# BSPD_rev11_v3.net
KiCad netlist of a schematic drawn in EAGLE
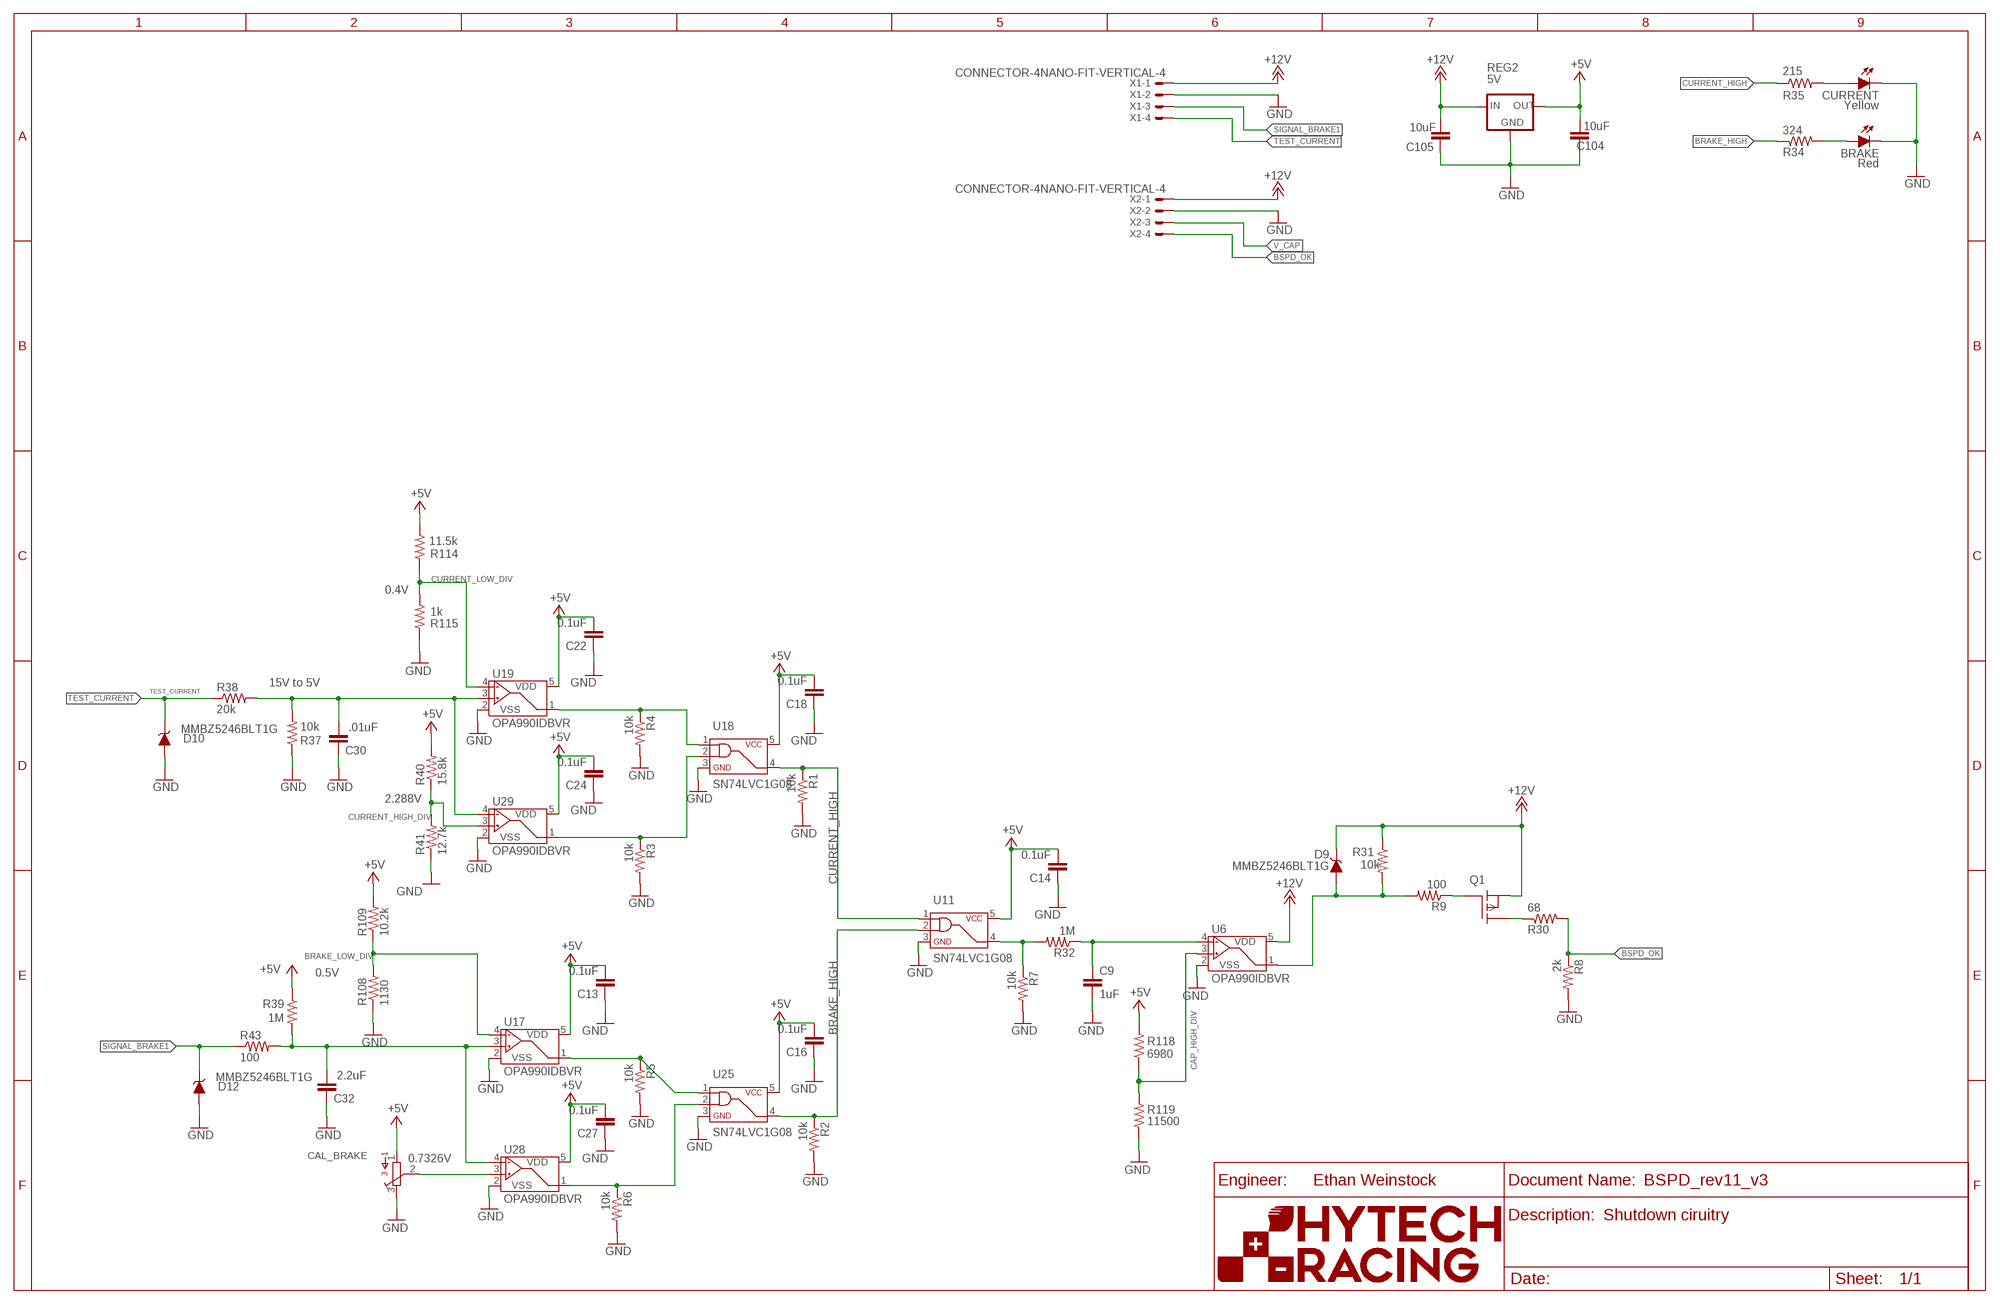
[diagram p0: schematic, sheet 1]

(export (version "E")
  (design (tool "Eeschema 10.0.6"))
  (components
    (comp (ref "BRAKE")
      (value "Red")
      (footprint "eagle-import:LED-805")
      (libsource (lib "eagle-import") (part "LED-0805"))
    )
    (comp (ref "C9")
      (value "1uF")
      (footprint "eagle-import:0603-CAP")
      (libsource (lib "eagle-import") (part "CAP0603-CAP"))
    )
    (comp (ref "C13")
      (value "0.1uF")
      (footprint "eagle-import:0603-CAP")
      (libsource (lib "eagle-import") (part "CAP0603-CAP"))
    )
    (comp (ref "C14")
      (value "0.1uF")
      (footprint "eagle-import:0603-CAP")
      (libsource (lib "eagle-import") (part "CAP0603-CAP"))
    )
    (comp (ref "C16")
      (value "0.1uF")
      (footprint "eagle-import:0603-CAP")
      (libsource (lib "eagle-import") (part "CAP0603-CAP"))
    )
    (comp (ref "C18")
      (value "0.1uF")
      (footprint "eagle-import:0603-CAP")
      (libsource (lib "eagle-import") (part "CAP0603-CAP"))
    )
    (comp (ref "C22")
      (value "0.1uF")
      (footprint "eagle-import:0603-CAP")
      (libsource (lib "eagle-import") (part "CAP0603-CAP"))
    )
    (comp (ref "C24")
      (value "0.1uF")
      (footprint "eagle-import:0603-CAP")
      (libsource (lib "eagle-import") (part "CAP0603-CAP"))
    )
    (comp (ref "C27")
      (value "0.1uF")
      (footprint "eagle-import:0603-CAP")
      (libsource (lib "eagle-import") (part "CAP0603-CAP"))
    )
    (comp (ref "C30")
      (value ".01uF")
      (footprint "eagle-import:0603-CAP")
      (libsource (lib "eagle-import") (part "CAP0603-CAP"))
    )
    (comp (ref "C32")
      (value "2.2uF")
      (footprint "eagle-import:0603-CAP")
      (libsource (lib "eagle-import") (part "CAP0603-CAP"))
    )
    (comp (ref "C104")
      (value "10uF")
      (footprint "eagle-import:0603-CAP")
      (libsource (lib "eagle-import") (part "CAP0603-CAP"))
    )
    (comp (ref "C105")
      (value "10uF")
      (footprint "eagle-import:0603-CAP")
      (libsource (lib "eagle-import") (part "CAP0603-CAP"))
    )
    (comp (ref "CAL_BRAKE")
      (value "TRIMPOT_3296C")
      (footprint "eagle-import:TRIMPOT_3296")
      (libsource (lib "eagle-import") (part "TRIMPOT_3296C"))
    )
    (comp (ref "CURRENT")
      (value "Yellow")
      (footprint "eagle-import:LED-805")
      (libsource (lib "eagle-import") (part "LED-0805"))
    )
    (comp (ref "D9")
      (value "MMBZ5246BLT1G")
      (footprint "eagle-import:SOT23")
      (libsource (lib "eagle-import") (part "DIODE_ZENER"))
    )
    (comp (ref "D10")
      (value "MMBZ5246BLT1G")
      (footprint "eagle-import:SOT23")
      (libsource (lib "eagle-import") (part "DIODE_ZENER"))
    )
    (comp (ref "D12")
      (value "MMBZ5246BLT1G")
      (footprint "eagle-import:SOT23")
      (libsource (lib "eagle-import") (part "DIODE_ZENER"))
    )
    (comp (ref "Q1")
      (value "P-CHANNEL_MOSFET_DMP3099L-7")
      (footprint "eagle-import:SOT23")
      (libsource (lib "eagle-import") (part "P-CHANNEL_MOSFET_DMP3099L-7"))
    )
    (comp (ref "R1")
      (value "10k")
      (footprint "eagle-import:0603-RES")
      (libsource (lib "eagle-import") (part "RESISTOR0603"))
    )
    (comp (ref "R2")
      (value "10k")
      (footprint "eagle-import:0603-RES")
      (libsource (lib "eagle-import") (part "RESISTOR0603"))
    )
    (comp (ref "R3")
      (value "10k")
      (footprint "eagle-import:0603-RES")
      (libsource (lib "eagle-import") (part "RESISTOR0603"))
    )
    (comp (ref "R4")
      (value "10k")
      (footprint "eagle-import:0603-RES")
      (libsource (lib "eagle-import") (part "RESISTOR0603"))
    )
    (comp (ref "R5")
      (value "10k")
      (footprint "eagle-import:0603-RES")
      (libsource (lib "eagle-import") (part "RESISTOR0603"))
    )
    (comp (ref "R6")
      (value "10k")
      (footprint "eagle-import:0603-RES")
      (libsource (lib "eagle-import") (part "RESISTOR0603"))
    )
    (comp (ref "R7")
      (value "10k")
      (footprint "eagle-import:0603-RES")
      (libsource (lib "eagle-import") (part "RESISTOR0603"))
    )
    (comp (ref "R8")
      (value "2k")
      (footprint "eagle-import:0603-RES")
      (libsource (lib "eagle-import") (part "RESISTOR0603"))
    )
    (comp (ref "R9")
      (value "100")
      (footprint "eagle-import:0603-RES")
      (libsource (lib "eagle-import") (part "RESISTOR0603"))
    )
    (comp (ref "R30")
      (value "68")
      (footprint "eagle-import:0603-RES")
      (libsource (lib "eagle-import") (part "RESISTOR0603"))
    )
    (comp (ref "R31")
      (value "10k")
      (footprint "eagle-import:0603-RES")
      (libsource (lib "eagle-import") (part "RESISTOR0603"))
    )
    (comp (ref "R32")
      (value "1M")
      (footprint "eagle-import:0603-RES")
      (libsource (lib "eagle-import") (part "RESISTOR0603"))
    )
    (comp (ref "R34")
      (value "324")
      (footprint "eagle-import:0603-RES")
      (libsource (lib "eagle-import") (part "RESISTOR0603"))
    )
    (comp (ref "R35")
      (value "215")
      (footprint "eagle-import:0603-RES")
      (libsource (lib "eagle-import") (part "RESISTOR0603"))
    )
    (comp (ref "R37")
      (value "10k")
      (footprint "eagle-import:0603-RES")
      (libsource (lib "eagle-import") (part "RESISTOR0603"))
    )
    (comp (ref "R38")
      (value "20k")
      (footprint "eagle-import:0603-RES")
      (libsource (lib "eagle-import") (part "RESISTOR0603"))
    )
    (comp (ref "R39")
      (value "1M")
      (footprint "eagle-import:0603-RES")
      (libsource (lib "eagle-import") (part "RESISTOR0603"))
    )
    (comp (ref "R40")
      (value "15.8k")
      (footprint "eagle-import:0603-RES")
      (libsource (lib "eagle-import") (part "RESISTOR0603"))
    )
    (comp (ref "R41")
      (value "12.7k")
      (footprint "eagle-import:0603-RES")
      (libsource (lib "eagle-import") (part "RESISTOR0603"))
    )
    (comp (ref "R43")
      (value "100")
      (footprint "eagle-import:0603-RES")
      (libsource (lib "eagle-import") (part "RESISTOR0603"))
    )
    (comp (ref "R108")
      (value "1130")
      (footprint "eagle-import:0603-RES")
      (libsource (lib "eagle-import") (part "RESISTOR0603"))
    )
    (comp (ref "R109")
      (value "10.2k")
      (footprint "eagle-import:0603-RES")
      (libsource (lib "eagle-import") (part "RESISTOR0603"))
    )
    (comp (ref "R114")
      (value "11.5k")
      (footprint "eagle-import:0603-RES")
      (libsource (lib "eagle-import") (part "RESISTOR0603"))
    )
    (comp (ref "R115")
      (value "1k")
      (footprint "eagle-import:0603-RES")
      (libsource (lib "eagle-import") (part "RESISTOR0603"))
    )
    (comp (ref "R118")
      (value "6980")
      (footprint "eagle-import:0603-RES")
      (libsource (lib "eagle-import") (part "RESISTOR0603"))
    )
    (comp (ref "R119")
      (value "11500")
      (footprint "eagle-import:0603-RES")
      (libsource (lib "eagle-import") (part "RESISTOR0603"))
    )
    (comp (ref "REG2")
      (value "5V")
      (footprint "eagle-import:OKI-78SR")
      (libsource (lib "eagle-import") (part "OKI-78SR-5"))
    )
    (comp (ref "U6")
      (value "OPA990IDBVR")
      (footprint "eagle-import:SOT-23-5")
      (libsource (lib "eagle-import") (part "OPA990IDBVR"))
    )
    (comp (ref "U11")
      (value "SN74LVC1G08")
      (footprint "eagle-import:SOT-23-5")
      (libsource (lib "eagle-import") (part "SN74LVC1G08"))
    )
    (comp (ref "U17")
      (value "OPA990IDBVR")
      (footprint "eagle-import:SOT-23-5")
      (libsource (lib "eagle-import") (part "OPA990IDBVR"))
    )
    (comp (ref "U18")
      (value "SN74LVC1G08")
      (footprint "eagle-import:SOT-23-5")
      (libsource (lib "eagle-import") (part "SN74LVC1G08"))
    )
    (comp (ref "U19")
      (value "OPA990IDBVR")
      (footprint "eagle-import:SOT-23-5")
      (libsource (lib "eagle-import") (part "OPA990IDBVR"))
    )
    (comp (ref "U25")
      (value "SN74LVC1G08")
      (footprint "eagle-import:SOT-23-5")
      (libsource (lib "eagle-import") (part "SN74LVC1G08"))
    )
    (comp (ref "U28")
      (value "OPA990IDBVR")
      (footprint "eagle-import:SOT-23-5")
      (libsource (lib "eagle-import") (part "OPA990IDBVR"))
    )
    (comp (ref "U29")
      (value "OPA990IDBVR")
      (footprint "eagle-import:SOT-23-5")
      (libsource (lib "eagle-import") (part "OPA990IDBVR"))
    )
    (comp (ref "X1")
      (value "CONNECTOR-4NANO-FIT-VERTICAL-4")
      (footprint "eagle-import:NANO-FIT_VERTICAL-4")
      (libsource (lib "eagle-import") (part "CONNECTOR-4NANO-FIT-VERTICAL-4"))
    )
    (comp (ref "X2")
      (value "CONNECTOR-4NANO-FIT-VERTICAL-4")
      (footprint "eagle-import:NANO-FIT_VERTICAL-4")
      (libsource (lib "eagle-import") (part "CONNECTOR-4NANO-FIT-VERTICAL-4"))
    )
  )
  (nets
    (net (code "1") (name "+5V") (class "Default")
      (node (ref "C104") (pin "2") (pinfunction "2_2") (pintype "passive"))
      (node (ref "C13") (pin "2") (pinfunction "2_2") (pintype "passive"))
      (node (ref "C14") (pin "2") (pinfunction "2_2") (pintype "passive"))
      (node (ref "C16") (pin "2") (pinfunction "2_2") (pintype "passive"))
      (node (ref "C18") (pin "2") (pinfunction "2_2") (pintype "passive"))
      (node (ref "C22") (pin "2") (pinfunction "2_2") (pintype "passive"))
      (node (ref "C24") (pin "2") (pinfunction "2_2") (pintype "passive"))
      (node (ref "C27") (pin "2") (pinfunction "2_2") (pintype "passive"))
      (node (ref "CAL_BRAKE") (pin "1") (pinfunction "1_1") (pintype "passive"))
      (node (ref "R109") (pin "2") (pinfunction "2_2") (pintype "passive"))
      (node (ref "R114") (pin "2") (pinfunction "2_2") (pintype "passive"))
      (node (ref "R118") (pin "2") (pinfunction "2_2") (pintype "passive"))
      (node (ref "R39") (pin "1") (pinfunction "1_1") (pintype "passive"))
      (node (ref "R40") (pin "2") (pinfunction "2_2") (pintype "passive"))
      (node (ref "REG2") (pin "3") (pinfunction "OUT_3") (pintype "passive"))
      (node (ref "U11") (pin "5") (pinfunction "5_5") (pintype "passive"))
      (node (ref "U17") (pin "5") (pinfunction "VDD_5") (pintype "passive"))
      (node (ref "U18") (pin "5") (pinfunction "5_5") (pintype "passive"))
      (node (ref "U19") (pin "5") (pinfunction "VDD_5") (pintype "passive"))
      (node (ref "U25") (pin "5") (pinfunction "5_5") (pintype "passive"))
      (node (ref "U28") (pin "5") (pinfunction "VDD_5") (pintype "passive"))
      (node (ref "U29") (pin "5") (pinfunction "VDD_5") (pintype "passive"))
    )
    (net (code "2") (name "+12V") (class "Default")
      (node (ref "C105") (pin "2") (pinfunction "2_2") (pintype "passive"))
      (node (ref "D9") (pin "3") (pinfunction "C_3") (pintype "passive"))
      (node (ref "Q1") (pin "2") (pinfunction "S_2") (pintype "passive"))
      (node (ref "R31") (pin "1") (pinfunction "1_1") (pintype "passive"))
      (node (ref "REG2") (pin "1") (pinfunction "IN_1") (pintype "input"))
      (node (ref "U6") (pin "5") (pinfunction "VDD_5") (pintype "passive"))
      (node (ref "X1") (pin "P$1") (pinfunction "S_P$1") (pintype "passive"))
      (node (ref "X2") (pin "P$1") (pinfunction "S_P$1") (pintype "passive"))
    )
    (net (code "3") (name "/BRAKE_LOW_DIV") (class "Default")
      (node (ref "R108") (pin "2") (pinfunction "2_2") (pintype "passive"))
      (node (ref "R109") (pin "1") (pinfunction "1_1") (pintype "passive"))
      (node (ref "U17") (pin "4") (pinfunction "VIN-_4") (pintype "passive"))
    )
    (net (code "4") (name "/CAP_HIGH_DIV") (class "Default")
      (node (ref "R118") (pin "1") (pinfunction "1_1") (pintype "passive"))
      (node (ref "R119") (pin "2") (pinfunction "2_2") (pintype "passive"))
      (node (ref "U6") (pin "3") (pinfunction "VIN+_3") (pintype "passive"))
    )
    (net (code "5") (name "/CURRENT_HIGH_DIV") (class "Default")
      (node (ref "R40") (pin "1") (pinfunction "1_1") (pintype "passive"))
      (node (ref "R41") (pin "2") (pinfunction "2_2") (pintype "passive"))
      (node (ref "U29") (pin "3") (pinfunction "VIN+_3") (pintype "passive"))
    )
    (net (code "6") (name "/CURRENT_LOW_DIV") (class "Default")
      (node (ref "R114") (pin "1") (pinfunction "1_1") (pintype "passive"))
      (node (ref "R115") (pin "2") (pinfunction "2_2") (pintype "passive"))
      (node (ref "U19") (pin "4") (pinfunction "VIN-_4") (pintype "passive"))
    )
    (net (code "7") (name "BRAKE_HIGH") (class "Default")
      (node (ref "R2") (pin "1") (pinfunction "1_1") (pintype "passive"))
      (node (ref "R34") (pin "1") (pinfunction "1_1") (pintype "passive"))
      (node (ref "U11") (pin "2") (pinfunction "2_2") (pintype "passive"))
      (node (ref "U25") (pin "4") (pinfunction "4_4") (pintype "passive"))
    )
    (net (code "8") (name "BSPD_OK") (class "Default")
      (node (ref "R30") (pin "2") (pinfunction "2_2") (pintype "passive"))
      (node (ref "R8") (pin "1") (pinfunction "1_1") (pintype "passive"))
      (node (ref "X2") (pin "P$4") (pinfunction "S_P$4") (pintype "passive"))
    )
    (net (code "9") (name "CURRENT_HIGH") (class "Default")
      (node (ref "R1") (pin "1") (pinfunction "1_1") (pintype "passive"))
      (node (ref "R35") (pin "1") (pinfunction "1_1") (pintype "passive"))
      (node (ref "U11") (pin "1") (pinfunction "1_1") (pintype "passive"))
      (node (ref "U18") (pin "4") (pinfunction "4_4") (pintype "passive"))
    )
    (net (code "10") (name "GND") (class "Default")
      (node (ref "BRAKE") (pin "C") (pinfunction "C_C") (pintype "passive"))
      (node (ref "C104") (pin "1") (pinfunction "1_1") (pintype "passive"))
      (node (ref "C105") (pin "1") (pinfunction "1_1") (pintype "passive"))
      (node (ref "C13") (pin "1") (pinfunction "1_1") (pintype "passive"))
      (node (ref "C14") (pin "1") (pinfunction "1_1") (pintype "passive"))
      (node (ref "C16") (pin "1") (pinfunction "1_1") (pintype "passive"))
      (node (ref "C18") (pin "1") (pinfunction "1_1") (pintype "passive"))
      (node (ref "C22") (pin "1") (pinfunction "1_1") (pintype "passive"))
      (node (ref "C24") (pin "1") (pinfunction "1_1") (pintype "passive"))
      (node (ref "C27") (pin "1") (pinfunction "1_1") (pintype "passive"))
      (node (ref "C30") (pin "1") (pinfunction "1_1") (pintype "passive"))
      (node (ref "C32") (pin "1") (pinfunction "1_1") (pintype "passive"))
      (node (ref "C9") (pin "2") (pinfunction "2_2") (pintype "passive"))
      (node (ref "CAL_BRAKE") (pin "3") (pinfunction "3_3") (pintype "passive"))
      (node (ref "CURRENT") (pin "C") (pinfunction "C_C") (pintype "passive"))
      (node (ref "D10") (pin "1") (pinfunction "A_1") (pintype "passive"))
      (node (ref "D12") (pin "1") (pinfunction "A_1") (pintype "passive"))
      (node (ref "R1") (pin "2") (pinfunction "2_2") (pintype "passive"))
      (node (ref "R108") (pin "1") (pinfunction "1_1") (pintype "passive"))
      (node (ref "R115") (pin "1") (pinfunction "1_1") (pintype "passive"))
      (node (ref "R119") (pin "1") (pinfunction "1_1") (pintype "passive"))
      (node (ref "R2") (pin "2") (pinfunction "2_2") (pintype "passive"))
      (node (ref "R3") (pin "2") (pinfunction "2_2") (pintype "passive"))
      (node (ref "R37") (pin "1") (pinfunction "1_1") (pintype "passive"))
      (node (ref "R4") (pin "2") (pinfunction "2_2") (pintype "passive"))
      (node (ref "R41") (pin "1") (pinfunction "1_1") (pintype "passive"))
      (node (ref "R5") (pin "2") (pinfunction "2_2") (pintype "passive"))
      (node (ref "R6") (pin "2") (pinfunction "2_2") (pintype "passive"))
      (node (ref "R7") (pin "2") (pinfunction "2_2") (pintype "passive"))
      (node (ref "R8") (pin "2") (pinfunction "2_2") (pintype "passive"))
      (node (ref "REG2") (pin "2") (pinfunction "GND_2") (pintype "input"))
      (node (ref "U11") (pin "3") (pinfunction "3_3") (pintype "passive"))
      (node (ref "U17") (pin "2") (pinfunction "VSS_2") (pintype "passive"))
      (node (ref "U18") (pin "3") (pinfunction "3_3") (pintype "passive"))
      (node (ref "U19") (pin "2") (pinfunction "VSS_2") (pintype "passive"))
      (node (ref "U25") (pin "3") (pinfunction "3_3") (pintype "passive"))
      (node (ref "U28") (pin "2") (pinfunction "VSS_2") (pintype "passive"))
      (node (ref "U29") (pin "2") (pinfunction "VSS_2") (pintype "passive"))
      (node (ref "U6") (pin "2") (pinfunction "VSS_2") (pintype "passive"))
      (node (ref "X1") (pin "P$2") (pinfunction "S_P$2") (pintype "passive"))
      (node (ref "X2") (pin "P$2") (pinfunction "S_P$2") (pintype "passive"))
    )
    (net (code "11") (name "Net-(BRAKE-PadA)") (class "Default")
      (node (ref "BRAKE") (pin "A") (pinfunction "A_A") (pintype "passive"))
      (node (ref "R34") (pin "2") (pinfunction "2_2") (pintype "passive"))
    )
    (net (code "12") (name "Net-(CURRENT-PadA)") (class "Default")
      (node (ref "CURRENT") (pin "A") (pinfunction "A_A") (pintype "passive"))
      (node (ref "R35") (pin "2") (pinfunction "2_2") (pintype "passive"))
    )
    (net (code "13") (name "Net-(D9-A)") (class "Default")
      (node (ref "D9") (pin "1") (pinfunction "A_1") (pintype "passive"))
      (node (ref "R31") (pin "2") (pinfunction "2_2") (pintype "passive"))
      (node (ref "R9") (pin "2") (pinfunction "2_2") (pintype "passive"))
      (node (ref "U6") (pin "1") (pinfunction "VOUT_1") (pintype "passive"))
    )
    (net (code "14") (name "Net-(Q1-D)") (class "Default")
      (node (ref "Q1") (pin "3") (pinfunction "D_3") (pintype "passive"))
      (node (ref "R30") (pin "1") (pinfunction "1_1") (pintype "passive"))
    )
    (net (code "15") (name "Net-(Q1-G)") (class "Default")
      (node (ref "Q1") (pin "1") (pinfunction "G_1") (pintype "passive"))
      (node (ref "R9") (pin "1") (pinfunction "1_1") (pintype "passive"))
    )
    (net (code "16") (name "Net-(R32-Pad2)") (class "Default")
      (node (ref "R32") (pin "2") (pinfunction "2_2") (pintype "passive"))
      (node (ref "R7") (pin "1") (pinfunction "1_1") (pintype "passive"))
      (node (ref "U11") (pin "4") (pinfunction "4_4") (pintype "passive"))
    )
    (net (code "17") (name "Net-(U6-VIN-)") (class "Default")
      (node (ref "C9") (pin "1") (pinfunction "1_1") (pintype "passive"))
      (node (ref "R32") (pin "1") (pinfunction "1_1") (pintype "passive"))
      (node (ref "U6") (pin "4") (pinfunction "VIN-_4") (pintype "passive"))
    )
    (net (code "18") (name "Net-(U17-VIN+)") (class "Default")
      (node (ref "C32") (pin "2") (pinfunction "2_2") (pintype "passive"))
      (node (ref "R39") (pin "2") (pinfunction "2_2") (pintype "passive"))
      (node (ref "R43") (pin "2") (pinfunction "2_2") (pintype "passive"))
      (node (ref "U17") (pin "3") (pinfunction "VIN+_3") (pintype "passive"))
      (node (ref "U28") (pin "4") (pinfunction "VIN-_4") (pintype "passive"))
    )
    (net (code "19") (name "Net-(U17-VOUT)") (class "Default")
      (node (ref "R5") (pin "1") (pinfunction "1_1") (pintype "passive"))
      (node (ref "U17") (pin "1") (pinfunction "VOUT_1") (pintype "passive"))
      (node (ref "U25") (pin "1") (pinfunction "1_1") (pintype "passive"))
    )
    (net (code "20") (name "Net-(U19-VIN+)") (class "Default")
      (node (ref "C30") (pin "2") (pinfunction "2_2") (pintype "passive"))
      (node (ref "R37") (pin "2") (pinfunction "2_2") (pintype "passive"))
      (node (ref "R38") (pin "2") (pinfunction "2_2") (pintype "passive"))
      (node (ref "U19") (pin "3") (pinfunction "VIN+_3") (pintype "passive"))
      (node (ref "U29") (pin "4") (pinfunction "VIN-_4") (pintype "passive"))
    )
    (net (code "21") (name "Net-(U19-VOUT)") (class "Default")
      (node (ref "R4") (pin "1") (pinfunction "1_1") (pintype "passive"))
      (node (ref "U18") (pin "1") (pinfunction "1_1") (pintype "passive"))
      (node (ref "U19") (pin "1") (pinfunction "VOUT_1") (pintype "passive"))
    )
    (net (code "22") (name "Net-(U28-VIN+)") (class "Default")
      (node (ref "CAL_BRAKE") (pin "2") (pinfunction "2_2") (pintype "passive"))
      (node (ref "U28") (pin "3") (pinfunction "VIN+_3") (pintype "passive"))
    )
    (net (code "23") (name "Net-(U28-VOUT)") (class "Default")
      (node (ref "R6") (pin "1") (pinfunction "1_1") (pintype "passive"))
      (node (ref "U25") (pin "2") (pinfunction "2_2") (pintype "passive"))
      (node (ref "U28") (pin "1") (pinfunction "VOUT_1") (pintype "passive"))
    )
    (net (code "24") (name "Net-(U29-VOUT)") (class "Default")
      (node (ref "R3") (pin "1") (pinfunction "1_1") (pintype "passive"))
      (node (ref "U18") (pin "2") (pinfunction "2_2") (pintype "passive"))
      (node (ref "U29") (pin "1") (pinfunction "VOUT_1") (pintype "passive"))
    )
    (net (code "25") (name "SIGNAL_BRAKE1") (class "Default")
      (node (ref "D12") (pin "3") (pinfunction "C_3") (pintype "passive"))
      (node (ref "R43") (pin "1") (pinfunction "1_1") (pintype "passive"))
      (node (ref "X1") (pin "P$3") (pinfunction "S_P$3") (pintype "passive"))
    )
    (net (code "26") (name "TEST_CURRENT") (class "Default")
      (node (ref "D10") (pin "3") (pinfunction "C_3") (pintype "passive"))
      (node (ref "R38") (pin "1") (pinfunction "1_1") (pintype "passive"))
      (node (ref "X1") (pin "P$4") (pinfunction "S_P$4") (pintype "passive"))
    )
    (net (code "27") (name "V_CAP") (class "Default")
      (node (ref "X2") (pin "P$3") (pinfunction "S_P$3") (pintype "passive"))
    )
  )
)
